# esp12f-dev-breakout.net
KiCad netlist of a schematic drawn in EAGLE
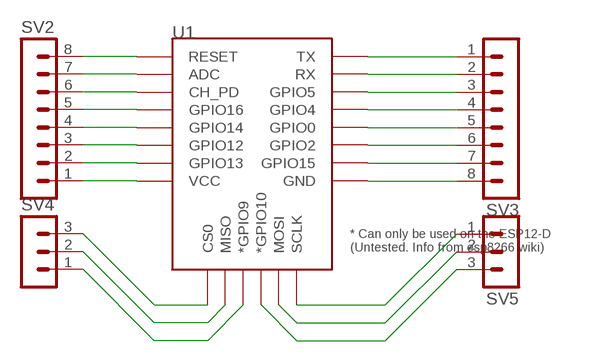
[diagram p0: schematic, sheet 1]

(export (version "E")
  (design (tool "Eeschema 10.0.6"))
  (components
    (comp (ref "SV2")
      (value "MA08-1")
      (footprint "eagle-import:MA08-1")
      (libsource (lib "eagle-import") (part "MA08-1"))
    )
    (comp (ref "SV3")
      (value "MA08-1")
      (footprint "eagle-import:MA08-1")
      (libsource (lib "eagle-import") (part "MA08-1"))
    )
    (comp (ref "SV4")
      (value "MA03-1")
      (footprint "eagle-import:MA03-1")
      (libsource (lib "eagle-import") (part "MA03-1"))
    )
    (comp (ref "SV5")
      (value "MA03-1")
      (footprint "eagle-import:MA03-1")
      (libsource (lib "eagle-import") (part "MA03-1"))
    )
    (comp (ref "U1")
      (value "ESP12ESMD")
      (footprint "eagle-import:ESP12E-SMD")
      (libsource (lib "eagle-import") (part "ESP12ESMD"))
    )
  )
  (nets
    (net (code "1") (name "Net-(SV2-Pad1)") (class "Default")
      (node (ref "SV2") (pin "1") (pinfunction "1_1") (pintype "passive"))
      (node (ref "U1") (pin "VCC") (pinfunction "VCC_VCC") (pintype "bidirectional"))
    )
    (net (code "2") (name "Net-(SV2-Pad2)") (class "Default")
      (node (ref "SV2") (pin "2") (pinfunction "2_2") (pintype "passive"))
      (node (ref "U1") (pin "GPIO13") (pinfunction "GPIO13_GPIO13") (pintype "bidirectional"))
    )
    (net (code "3") (name "Net-(SV2-Pad3)") (class "Default")
      (node (ref "SV2") (pin "3") (pinfunction "3_3") (pintype "passive"))
      (node (ref "U1") (pin "GPIO12") (pinfunction "GPIO12_GPIO12") (pintype "bidirectional"))
    )
    (net (code "4") (name "Net-(SV2-Pad4)") (class "Default")
      (node (ref "SV2") (pin "4") (pinfunction "4_4") (pintype "passive"))
      (node (ref "U1") (pin "GPIO14") (pinfunction "GPIO14_GPIO14") (pintype "bidirectional"))
    )
    (net (code "5") (name "Net-(SV2-Pad5)") (class "Default")
      (node (ref "SV2") (pin "5") (pinfunction "5_5") (pintype "passive"))
      (node (ref "U1") (pin "GPIO16") (pinfunction "GPIO16_GPIO16") (pintype "bidirectional"))
    )
    (net (code "6") (name "Net-(SV2-Pad6)") (class "Default")
      (node (ref "SV2") (pin "6") (pinfunction "6_6") (pintype "passive"))
      (node (ref "U1") (pin "CH_PD") (pinfunction "CH_PD_CH_PD") (pintype "bidirectional"))
    )
    (net (code "7") (name "Net-(SV2-Pad7)") (class "Default")
      (node (ref "SV2") (pin "7") (pinfunction "7_7") (pintype "passive"))
      (node (ref "U1") (pin "ADC") (pinfunction "ADC_ADC") (pintype "bidirectional"))
    )
    (net (code "8") (name "Net-(SV2-Pad8)") (class "Default")
      (node (ref "SV2") (pin "8") (pinfunction "8_8") (pintype "passive"))
      (node (ref "U1") (pin "RESET") (pinfunction "RESET_RESET") (pintype "bidirectional"))
    )
    (net (code "9") (name "Net-(SV3-Pad3)") (class "Default")
      (node (ref "SV3") (pin "3") (pinfunction "3_3") (pintype "passive"))
      (node (ref "U1") (pin "GPIO5") (pinfunction "GPIO5_GPIO5") (pintype "bidirectional"))
    )
    (net (code "10") (name "Net-(SV3-Pad4)") (class "Default")
      (node (ref "SV3") (pin "4") (pinfunction "4_4") (pintype "passive"))
      (node (ref "U1") (pin "GPIO4") (pinfunction "GPIO4_GPIO4") (pintype "bidirectional"))
    )
    (net (code "11") (name "Net-(SV3-Pad5)") (class "Default")
      (node (ref "SV3") (pin "5") (pinfunction "5_5") (pintype "passive"))
      (node (ref "U1") (pin "GPIO0") (pinfunction "GPIO0_GPIO0") (pintype "bidirectional"))
    )
    (net (code "12") (name "Net-(SV3-Pad6)") (class "Default")
      (node (ref "SV3") (pin "6") (pinfunction "6_6") (pintype "passive"))
      (node (ref "U1") (pin "GPIO2") (pinfunction "GPIO2_GPIO2") (pintype "bidirectional"))
    )
    (net (code "13") (name "Net-(SV3-Pad7)") (class "Default")
      (node (ref "SV3") (pin "7") (pinfunction "7_7") (pintype "passive"))
      (node (ref "U1") (pin "GPIO15") (pinfunction "GPIO15_GPIO15") (pintype "bidirectional"))
    )
    (net (code "14") (name "Net-(SV3-Pad8)") (class "Default")
      (node (ref "SV3") (pin "8") (pinfunction "8_8") (pintype "passive"))
      (node (ref "U1") (pin "GND") (pinfunction "GND_GND") (pintype "bidirectional"))
    )
    (net (code "15") (name "Net-(SV4-Pad2)") (class "Default")
      (node (ref "SV4") (pin "2") (pinfunction "2_2") (pintype "passive"))
      (node (ref "U1") (pin "MISO") (pinfunction "MISO_MISO") (pintype "bidirectional"))
    )
    (net (code "16") (name "Net-(SV4-Pad3)") (class "Default")
      (node (ref "SV4") (pin "3") (pinfunction "3_3") (pintype "passive"))
      (node (ref "U1") (pin "CS0") (pinfunction "CS0_CS0") (pintype "bidirectional"))
    )
    (net (code "17") (name "Net-(SV5-Pad1)") (class "Default")
      (node (ref "SV5") (pin "1") (pinfunction "1_1") (pintype "passive"))
      (node (ref "U1") (pin "SCLK") (pinfunction "SCLK_SCLK") (pintype "bidirectional"))
    )
    (net (code "18") (name "Net-(SV5-Pad2)") (class "Default")
      (node (ref "SV5") (pin "2") (pinfunction "2_2") (pintype "passive"))
      (node (ref "U1") (pin "MOSI") (pinfunction "MOSI_MOSI") (pintype "bidirectional"))
    )
    (net (code "19") (name "Net-(U1-*GPIO9)") (class "Default")
      (node (ref "SV4") (pin "1") (pinfunction "1_1") (pintype "passive"))
      (node (ref "U1") (pin "GPIO9") (pinfunction "*GPIO9_GPIO9") (pintype "bidirectional"))
    )
    (net (code "20") (name "Net-(U1-*GPIO10)") (class "Default")
      (node (ref "SV5") (pin "3") (pinfunction "3_3") (pintype "passive"))
      (node (ref "U1") (pin "GPIO10") (pinfunction "*GPIO10_GPIO10") (pintype "bidirectional"))
    )
    (net (code "21") (name "Net-(U1-RX)") (class "Default")
      (node (ref "SV3") (pin "2") (pinfunction "2_2") (pintype "passive"))
      (node (ref "U1") (pin "RXD0") (pinfunction "RX_RXD0") (pintype "bidirectional"))
    )
    (net (code "22") (name "Net-(U1-TX)") (class "Default")
      (node (ref "SV3") (pin "1") (pinfunction "1_1") (pintype "passive"))
      (node (ref "U1") (pin "TXD0") (pinfunction "TX_TXD0") (pintype "bidirectional"))
    )
  )
)
